# od808.net
KiCad netlist of a schematic drawn in EAGLE
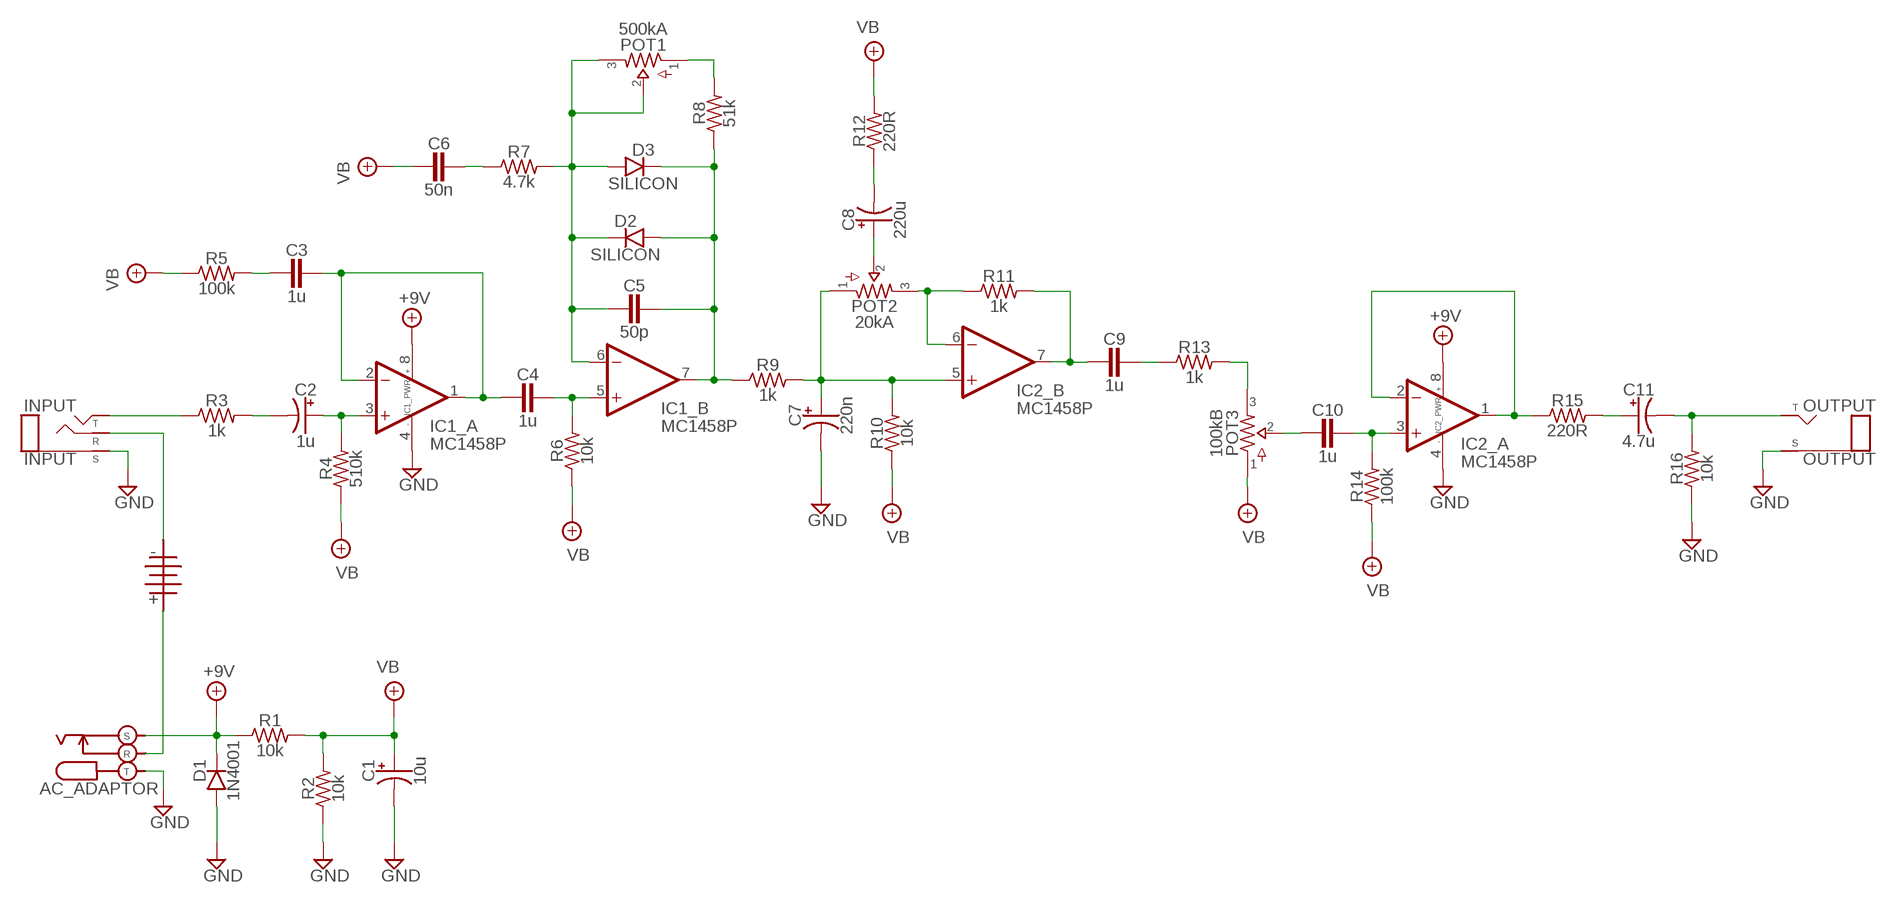
[diagram p0: schematic, sheet 1]

(export (version "E")
  (design (tool "Eeschema 10.0.6"))
  (components
    (comp (ref "AC_ADAPTOR")
      (value "DCJACK")
      (footprint "eagle-import:DC_KOBICONN")
      (libsource (lib "eagle-import") (part "DC_KOBICONN"))
    )
    (comp (ref "BATTERY")
      (value "BATTERY")
      (footprint "eagle-import:TWO_PADS")
      (libsource (lib "eagle-import") (part "BATTERY"))
    )
    (comp (ref "C1")
      (value "10u")
      (footprint "eagle-import:050_020")
      (libsource (lib "eagle-import") (part "0500"))
    )
    (comp (ref "C2")
      (value "1u")
      (footprint "eagle-import:050_020")
      (libsource (lib "eagle-import") (part "0500"))
    )
    (comp (ref "C3")
      (value "1u")
      (footprint "eagle-import:BOX_SMALL")
      (libsource (lib "eagle-import") (part "CER/FILMBOX.1"))
    )
    (comp (ref "C4")
      (value "1u")
      (footprint "eagle-import:BOX_SMALL")
      (libsource (lib "eagle-import") (part "CER/FILMBOX.1"))
    )
    (comp (ref "C5")
      (value "50p")
      (footprint "eagle-import:BOX_SMALL")
      (libsource (lib "eagle-import") (part "CER/FILMBOX.1"))
    )
    (comp (ref "C6")
      (value "50n")
      (footprint "eagle-import:BOX_SMALL")
      (libsource (lib "eagle-import") (part "CER/FILMBOX.1"))
    )
    (comp (ref "C7")
      (value "220n")
      (footprint "eagle-import:050_020")
      (libsource (lib "eagle-import") (part "0500"))
    )
    (comp (ref "C8")
      (value "220u")
      (footprint "eagle-import:050_020")
      (libsource (lib "eagle-import") (part "0500"))
    )
    (comp (ref "C9")
      (value "1u")
      (footprint "eagle-import:BOX_SMALL")
      (libsource (lib "eagle-import") (part "CER/FILMBOX.1"))
    )
    (comp (ref "C10")
      (value "1u")
      (footprint "eagle-import:BOX_SMALL")
      (libsource (lib "eagle-import") (part "CER/FILMBOX.1"))
    )
    (comp (ref "C11")
      (value "4.7u")
      (footprint "eagle-import:050_020")
      (libsource (lib "eagle-import") (part "0500"))
    )
    (comp (ref "D1")
      (value "1N4001")
      (footprint "eagle-import:DO35-2")
      (libsource (lib "eagle-import") (part "DO35.2"))
    )
    (comp (ref "D2")
      (value "SILICON")
      (footprint "eagle-import:DO35-2")
      (libsource (lib "eagle-import") (part "DO35.2"))
    )
    (comp (ref "D3")
      (value "SILICON")
      (footprint "eagle-import:DO35-2")
      (libsource (lib "eagle-import") (part "DO35.2"))
    )
    (comp (ref "IC1")
      (value "MC1458P")
      (footprint "eagle-import:DIL0")
      (libsource (lib "eagle-import") (part "DUALTH"))
    )
    (comp (ref "IC2")
      (value "MC1458P")
      (footprint "eagle-import:DIL0")
      (libsource (lib "eagle-import") (part "DUALTH"))
    )
    (comp (ref "INPUT")
      (value "INPUT")
      (footprint "eagle-import:THREEPADS")
      (libsource (lib "eagle-import") (part "STEREO3PADS"))
    )
    (comp (ref "OUTPUT")
      (value "OUTPUT")
      (footprint "eagle-import:TWO_PADS")
      (libsource (lib "eagle-import") (part "MONO"))
    )
    (comp (ref "POT1")
      (value "500kA")
      (footprint "eagle-import:16MM")
      (libsource (lib "eagle-import") (part "POTS16MM"))
    )
    (comp (ref "POT2")
      (value "20kA")
      (footprint "eagle-import:16MM")
      (libsource (lib "eagle-import") (part "POTS16MM"))
    )
    (comp (ref "POT3")
      (value "100kB")
      (footprint "eagle-import:16MM")
      (libsource (lib "eagle-import") (part "POTS16MM"))
    )
    (comp (ref "R1")
      (value "10k")
      (footprint "eagle-import:R0207_3")
      (libsource (lib "eagle-import") (part "R_.3B"))
    )
    (comp (ref "R2")
      (value "10k")
      (footprint "eagle-import:R0207_3")
      (libsource (lib "eagle-import") (part "R_.3B"))
    )
    (comp (ref "R3")
      (value "1k")
      (footprint "eagle-import:R0207_3")
      (libsource (lib "eagle-import") (part "R_.3B"))
    )
    (comp (ref "R4")
      (value "510k")
      (footprint "eagle-import:R0207_3")
      (libsource (lib "eagle-import") (part "R_.3B"))
    )
    (comp (ref "R5")
      (value "100k")
      (footprint "eagle-import:R0207_3")
      (libsource (lib "eagle-import") (part "R_.3B"))
    )
    (comp (ref "R6")
      (value "10k")
      (footprint "eagle-import:R0207_3")
      (libsource (lib "eagle-import") (part "R_.3B"))
    )
    (comp (ref "R7")
      (value "4.7k")
      (footprint "eagle-import:R0207_3")
      (libsource (lib "eagle-import") (part "R_.3B"))
    )
    (comp (ref "R8")
      (value "51k")
      (footprint "eagle-import:R0207_3")
      (libsource (lib "eagle-import") (part "R_.3B"))
    )
    (comp (ref "R9")
      (value "1k")
      (footprint "eagle-import:R0207_3")
      (libsource (lib "eagle-import") (part "R_.3B"))
    )
    (comp (ref "R10")
      (value "10k")
      (footprint "eagle-import:R0207_3")
      (libsource (lib "eagle-import") (part "R_.3B"))
    )
    (comp (ref "R11")
      (value "1k")
      (footprint "eagle-import:R0207_3")
      (libsource (lib "eagle-import") (part "R_.3B"))
    )
    (comp (ref "R12")
      (value "220R")
      (footprint "eagle-import:R0207_3")
      (libsource (lib "eagle-import") (part "R_.3B"))
    )
    (comp (ref "R13")
      (value "1k")
      (footprint "eagle-import:R0207_3")
      (libsource (lib "eagle-import") (part "R_.3B"))
    )
    (comp (ref "R14")
      (value "100k")
      (footprint "eagle-import:R0207_3")
      (libsource (lib "eagle-import") (part "R_.3B"))
    )
    (comp (ref "R15")
      (value "220R")
      (footprint "eagle-import:R0207_3")
      (libsource (lib "eagle-import") (part "R_.3B"))
    )
    (comp (ref "R16")
      (value "10k")
      (footprint "eagle-import:R0207_3")
      (libsource (lib "eagle-import") (part "R_.3B"))
    )
  )
  (nets
    (net (code "1") (name "+9V") (class "Default")
      (node (ref "AC_ADAPTOR") (pin "S") (pinfunction "S_S") (pintype "bidirectional"))
      (node (ref "D1") (pin "C") (pinfunction "C_C") (pintype "passive"))
      (node (ref "IC1") (pin "8") (pinfunction "V+_8") (pintype "power_in"))
      (node (ref "IC2") (pin "8") (pinfunction "V+_8") (pintype "power_in"))
      (node (ref "R1") (pin "1") (pinfunction "1_1") (pintype "passive"))
    )
    (net (code "2") (name "GND") (class "Default")
      (node (ref "AC_ADAPTOR") (pin "T") (pinfunction "T_T") (pintype "bidirectional"))
      (node (ref "C1") (pin "-") (pinfunction "-_-") (pintype "passive"))
      (node (ref "C7") (pin "-") (pinfunction "-_-") (pintype "passive"))
      (node (ref "D1") (pin "A") (pinfunction "A_A") (pintype "passive"))
      (node (ref "IC1") (pin "4") (pinfunction "V-_4") (pintype "power_in"))
      (node (ref "IC2") (pin "4") (pinfunction "V-_4") (pintype "power_in"))
      (node (ref "INPUT") (pin "SLEEVE") (pinfunction "S_SLEEVE") (pintype "passive"))
      (node (ref "OUTPUT") (pin "S") (pinfunction "SLEEVE_S") (pintype "passive"))
      (node (ref "R16") (pin "1") (pinfunction "1_1") (pintype "passive"))
      (node (ref "R2") (pin "1") (pinfunction "1_1") (pintype "passive"))
    )
    (net (code "3") (name "Net-(BATTERY-P$1)") (class "Default")
      (node (ref "AC_ADAPTOR") (pin "R") (pinfunction "R_R") (pintype "bidirectional"))
      (node (ref "BATTERY") (pin "T") (pinfunction "P$1_T") (pintype "bidirectional"))
    )
    (net (code "4") (name "Net-(BATTERY-P$2)") (class "Default")
      (node (ref "BATTERY") (pin "S") (pinfunction "P$2_S") (pintype "bidirectional"))
      (node (ref "INPUT") (pin "RING") (pinfunction "R_RING") (pintype "passive"))
    )
    (net (code "5") (name "Net-(C2-Pad-)") (class "Default")
      (node (ref "C2") (pin "-") (pinfunction "-_-") (pintype "passive"))
      (node (ref "R3") (pin "2") (pinfunction "2_2") (pintype "passive"))
    )
    (net (code "6") (name "Net-(C3-Pad2)") (class "Default")
      (node (ref "C3") (pin "2") (pinfunction "2_2") (pintype "passive"))
      (node (ref "R5") (pin "2") (pinfunction "2_2") (pintype "passive"))
    )
    (net (code "7") (name "Net-(C6-Pad1)") (class "Default")
      (node (ref "C6") (pin "1") (pinfunction "1_1") (pintype "passive"))
      (node (ref "R7") (pin "1") (pinfunction "1_1") (pintype "passive"))
    )
    (net (code "8") (name "Net-(C8-Pad+)") (class "Default")
      (node (ref "C8") (pin "+") (pinfunction "+_+") (pintype "passive"))
      (node (ref "POT2") (pin "2") (pinfunction "2_2") (pintype "passive"))
    )
    (net (code "9") (name "Net-(C8-Pad-)") (class "Default")
      (node (ref "C8") (pin "-") (pinfunction "-_-") (pintype "passive"))
      (node (ref "R12") (pin "1") (pinfunction "1_1") (pintype "passive"))
    )
    (net (code "10") (name "Net-(C9-Pad1)") (class "Default")
      (node (ref "C9") (pin "1") (pinfunction "1_1") (pintype "passive"))
      (node (ref "R13") (pin "1") (pinfunction "1_1") (pintype "passive"))
    )
    (net (code "11") (name "Net-(C10-Pad2)") (class "Default")
      (node (ref "C10") (pin "2") (pinfunction "2_2") (pintype "passive"))
      (node (ref "POT3") (pin "2") (pinfunction "2_2") (pintype "passive"))
    )
    (net (code "12") (name "Net-(C11-Pad+)") (class "Default")
      (node (ref "C11") (pin "+") (pinfunction "+_+") (pintype "passive"))
      (node (ref "R15") (pin "2") (pinfunction "2_2") (pintype "passive"))
    )
    (net (code "13") (name "Net-(IC1A-+IN)") (class "Default")
      (node (ref "C2") (pin "+") (pinfunction "+_+") (pintype "passive"))
      (node (ref "IC1") (pin "3") (pinfunction "+IN_3") (pintype "input"))
      (node (ref "R4") (pin "2") (pinfunction "2_2") (pintype "passive"))
    )
    (net (code "14") (name "Net-(IC1A--IN)") (class "Default")
      (node (ref "C3") (pin "1") (pinfunction "1_1") (pintype "passive"))
      (node (ref "C4") (pin "2") (pinfunction "2_2") (pintype "passive"))
      (node (ref "IC1") (pin "1") (pinfunction "OUT_1") (pintype "output"))
      (node (ref "IC1") (pin "2") (pinfunction "-IN_2") (pintype "input"))
    )
    (net (code "15") (name "Net-(IC1B-+IN)") (class "Default")
      (node (ref "C4") (pin "1") (pinfunction "1_1") (pintype "passive"))
      (node (ref "IC1") (pin "5") (pinfunction "+IN_5") (pintype "input"))
      (node (ref "R6") (pin "2") (pinfunction "2_2") (pintype "passive"))
    )
    (net (code "16") (name "Net-(IC1B--IN)") (class "Default")
      (node (ref "C5") (pin "2") (pinfunction "2_2") (pintype "passive"))
      (node (ref "D2") (pin "C") (pinfunction "C_C") (pintype "passive"))
      (node (ref "D3") (pin "A") (pinfunction "A_A") (pintype "passive"))
      (node (ref "IC1") (pin "6") (pinfunction "-IN_6") (pintype "input"))
      (node (ref "POT1") (pin "2") (pinfunction "2_2") (pintype "passive"))
      (node (ref "POT1") (pin "3") (pinfunction "3_3") (pintype "passive"))
      (node (ref "R7") (pin "2") (pinfunction "2_2") (pintype "passive"))
    )
    (net (code "17") (name "Net-(IC1B-OUT)") (class "Default")
      (node (ref "C5") (pin "1") (pinfunction "1_1") (pintype "passive"))
      (node (ref "D2") (pin "A") (pinfunction "A_A") (pintype "passive"))
      (node (ref "D3") (pin "C") (pinfunction "C_C") (pintype "passive"))
      (node (ref "IC1") (pin "7") (pinfunction "OUT_7") (pintype "output"))
      (node (ref "R8") (pin "1") (pinfunction "1_1") (pintype "passive"))
      (node (ref "R9") (pin "1") (pinfunction "1_1") (pintype "passive"))
    )
    (net (code "18") (name "Net-(IC2A-+IN)") (class "Default")
      (node (ref "C10") (pin "1") (pinfunction "1_1") (pintype "passive"))
      (node (ref "IC2") (pin "3") (pinfunction "+IN_3") (pintype "input"))
      (node (ref "R14") (pin "2") (pinfunction "2_2") (pintype "passive"))
    )
    (net (code "19") (name "Net-(IC2A--IN)") (class "Default")
      (node (ref "IC2") (pin "1") (pinfunction "OUT_1") (pintype "output"))
      (node (ref "IC2") (pin "2") (pinfunction "-IN_2") (pintype "input"))
      (node (ref "R15") (pin "1") (pinfunction "1_1") (pintype "passive"))
    )
    (net (code "20") (name "Net-(IC2B-+IN)") (class "Default")
      (node (ref "C7") (pin "+") (pinfunction "+_+") (pintype "passive"))
      (node (ref "IC2") (pin "5") (pinfunction "+IN_5") (pintype "input"))
      (node (ref "POT2") (pin "1") (pinfunction "1_1") (pintype "passive"))
      (node (ref "R10") (pin "2") (pinfunction "2_2") (pintype "passive"))
      (node (ref "R9") (pin "2") (pinfunction "2_2") (pintype "passive"))
    )
    (net (code "21") (name "Net-(IC2B--IN)") (class "Default")
      (node (ref "IC2") (pin "6") (pinfunction "-IN_6") (pintype "input"))
      (node (ref "POT2") (pin "3") (pinfunction "3_3") (pintype "passive"))
      (node (ref "R11") (pin "1") (pinfunction "1_1") (pintype "passive"))
    )
    (net (code "22") (name "Net-(IC2B-OUT)") (class "Default")
      (node (ref "C9") (pin "2") (pinfunction "2_2") (pintype "passive"))
      (node (ref "IC2") (pin "7") (pinfunction "OUT_7") (pintype "output"))
      (node (ref "R11") (pin "2") (pinfunction "2_2") (pintype "passive"))
    )
    (net (code "23") (name "Net-(INPUT-T)") (class "Default")
      (node (ref "INPUT") (pin "TIP") (pinfunction "T_TIP") (pintype "passive"))
      (node (ref "R3") (pin "1") (pinfunction "1_1") (pintype "passive"))
    )
    (net (code "24") (name "Net-(OUTPUT-TIP)") (class "Default")
      (node (ref "C11") (pin "-") (pinfunction "-_-") (pintype "passive"))
      (node (ref "OUTPUT") (pin "T") (pinfunction "TIP_T") (pintype "passive"))
      (node (ref "R16") (pin "2") (pinfunction "2_2") (pintype "passive"))
    )
    (net (code "25") (name "Net-(POT1-Pad1)") (class "Default")
      (node (ref "POT1") (pin "1") (pinfunction "1_1") (pintype "passive"))
      (node (ref "R8") (pin "2") (pinfunction "2_2") (pintype "passive"))
    )
    (net (code "26") (name "Net-(POT3-Pad3)") (class "Default")
      (node (ref "POT3") (pin "3") (pinfunction "3_3") (pintype "passive"))
      (node (ref "R13") (pin "2") (pinfunction "2_2") (pintype "passive"))
    )
    (net (code "27") (name "VB") (class "Default")
      (node (ref "C1") (pin "+") (pinfunction "+_+") (pintype "passive"))
      (node (ref "C6") (pin "2") (pinfunction "2_2") (pintype "passive"))
      (node (ref "POT3") (pin "1") (pinfunction "1_1") (pintype "passive"))
      (node (ref "R1") (pin "2") (pinfunction "2_2") (pintype "passive"))
      (node (ref "R10") (pin "1") (pinfunction "1_1") (pintype "passive"))
      (node (ref "R12") (pin "2") (pinfunction "2_2") (pintype "passive"))
      (node (ref "R14") (pin "1") (pinfunction "1_1") (pintype "passive"))
      (node (ref "R2") (pin "2") (pinfunction "2_2") (pintype "passive"))
      (node (ref "R4") (pin "1") (pinfunction "1_1") (pintype "passive"))
      (node (ref "R5") (pin "1") (pinfunction "1_1") (pintype "passive"))
      (node (ref "R6") (pin "1") (pinfunction "1_1") (pintype "passive"))
    )
  )
)
